# Power.net
KiCad netlist of a schematic drawn in Altium Designer
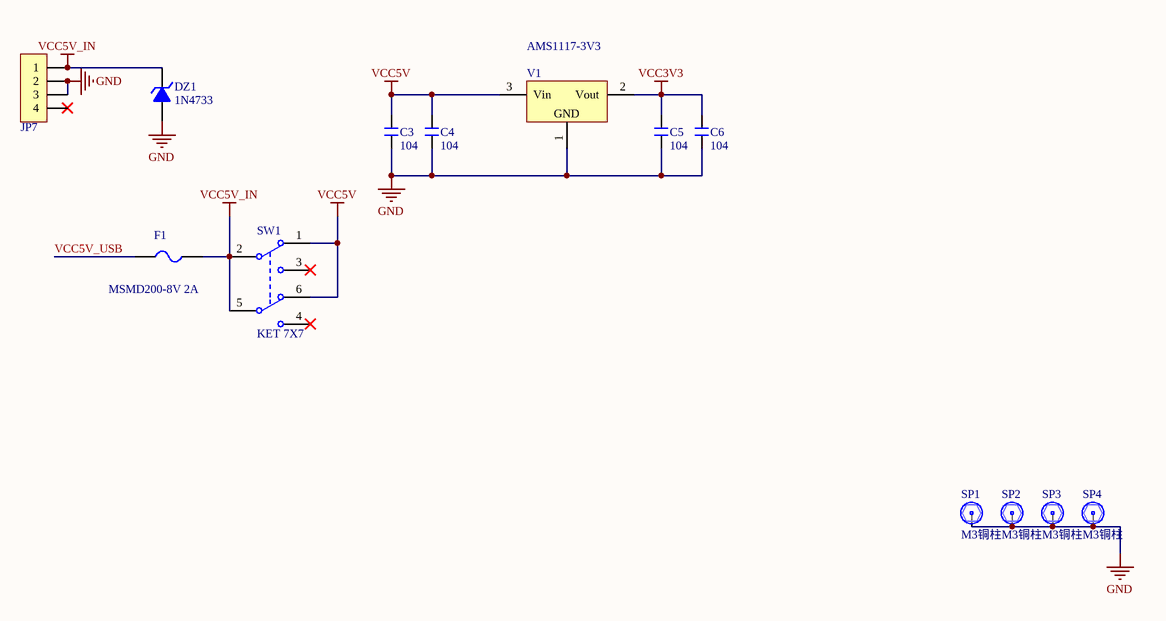
[diagram p0: Power.SchDoc]

(export (version "E")
  (design (tool "Eeschema 10.0.6"))
  (components
    (comp (ref "C3")
      (value "104")
      (footprint "C 1812_L")
      (description "无极性贴片电容")
      (fields (field (name "版权归属") "源创客"))
      (libsource (lib "3.1   - 电阻-电容-电感") (part "C"))
    )
    (comp (ref "C4")
      (value "104")
      (footprint "C 1812_L")
      (description "无极性贴片电容")
      (fields (field (name "版权归属") "源创客"))
      (libsource (lib "3.1   - 电阻-电容-电感") (part "C"))
    )
    (comp (ref "C5")
      (value "104")
      (footprint "C 1206_M")
      (description "无极性贴片电容")
      (fields (field (name "版权归属") "源创客"))
      (libsource (lib "3.1   - 电阻-电容-电感") (part "C"))
    )
    (comp (ref "C6")
      (value "104")
      (footprint "C 1206_M")
      (description "无极性贴片电容")
      (fields (field (name "版权归属") "源创客"))
      (libsource (lib "3.1   - 电阻-电容-电感") (part "C"))
    )
    (comp (ref "DZ1")
      (value "1N4733")
      (footprint "SMA")
      (description "5.1V/1W稳压管")
      (fields (field (name "版权归属") "源创客"))
      (libsource (lib "8.1   - 二极管-整流桥") (part "1N4733"))
    )
    (comp (ref "F1")
      (value "MSMD200-8V 2A")
      (footprint "FU 1210")
      (description "贴片保险丝")
      (fields (field (name "版权归属") "源创客"))
      (libsource (lib "10.1 - 保险丝-晶振") (part "FU"))
    )
    (comp (ref "JP7")
      (value "HDR-1X4")
      (footprint "VH3.96-LI-4P")
      (description "4P接插件")
      (fields (field (name "版权归属") "源创客"))
      (libsource (lib "4.8   - 接插件-脚距3.96") (part "Header 4"))
    )
    (comp (ref "SP1")
      (value "M3铜柱")
      (footprint "M3x4_L")
      (description "铜柱")
      (fields (field (name "版权归属") "源创客"))
      (libsource (lib "15.1 - 未分类器件") (part "铜柱小焊盘"))
    )
    (comp (ref "SP2")
      (value "M3铜柱")
      (footprint "M3x4_L")
      (description "铜柱")
      (fields (field (name "版权归属") "源创客"))
      (libsource (lib "15.1 - 未分类器件") (part "铜柱小焊盘"))
    )
    (comp (ref "SP3")
      (value "M3铜柱")
      (footprint "M3x4_L")
      (description "铜柱")
      (fields (field (name "版权归属") "源创客"))
      (libsource (lib "15.1 - 未分类器件") (part "铜柱小焊盘"))
    )
    (comp (ref "SP4")
      (value "M3铜柱")
      (footprint "M3x4_L")
      (description "铜柱")
      (fields (field (name "版权归属") "源创客"))
      (libsource (lib "15.1 - 未分类器件") (part "铜柱小焊盘"))
    )
    (comp (ref "SW1")
      (value "KET 7X7")
      (footprint "KFT DIP-7X7")
      (description "7*7自锁开关")
      (fields (field (name "版权归属") "源创客"))
      (libsource (lib "5.1   - 按键-开关") (part "KET 7X7"))
    )
    (comp (ref "V1")
      (value "AMS1117-3V3")
      (footprint "SOT223_L")
      (description "三端稳压芯片")
      (fields (field (name "版权归属") "源创客"))
      (libsource (lib "1.3   - 电源类芯片") (part "AMS1117"))
    )
  )
  (nets
    (net (code "1") (name "/VCC5V_USB") (class "Default")
      (node (ref "F1") (pin "1") (pinfunction "1_1") (pintype "passive"))
    )
    (net (code "2") (name "GND") (class "Default")
      (node (ref "C3") (pin "1") (pinfunction "1_1") (pintype "passive"))
      (node (ref "C4") (pin "1") (pinfunction "1_1") (pintype "passive"))
      (node (ref "C5") (pin "1") (pinfunction "1_1") (pintype "passive"))
      (node (ref "C6") (pin "1") (pinfunction "1_1") (pintype "passive"))
      (node (ref "DZ1") (pin "1") (pinfunction "A_1") (pintype "passive"))
      (node (ref "JP7") (pin "2") (pinfunction "2_2") (pintype "passive"))
      (node (ref "JP7") (pin "3") (pinfunction "3_3") (pintype "passive"))
      (node (ref "SP1") (pin "1") (pinfunction "1_1") (pintype "passive"))
      (node (ref "SP2") (pin "1") (pinfunction "1_1") (pintype "passive"))
      (node (ref "SP3") (pin "1") (pinfunction "1_1") (pintype "passive"))
      (node (ref "SP4") (pin "1") (pinfunction "1_1") (pintype "passive"))
      (node (ref "V1") (pin "1") (pinfunction "GND_1") (pintype "passive"))
    )
    (net (code "3") (name "VCC3V3") (class "Default")
      (node (ref "C5") (pin "2") (pinfunction "2_2") (pintype "passive"))
      (node (ref "C6") (pin "2") (pinfunction "2_2") (pintype "passive"))
      (node (ref "V1") (pin "2") (pinfunction "Vout_2") (pintype "passive"))
    )
    (net (code "4") (name "VCC5V") (class "Default")
      (node (ref "C3") (pin "2") (pinfunction "2_2") (pintype "passive"))
      (node (ref "C4") (pin "2") (pinfunction "2_2") (pintype "passive"))
      (node (ref "SW1") (pin "1") (pinfunction "NC1_1") (pintype "passive"))
      (node (ref "SW1") (pin "6") (pinfunction "NC2_6") (pintype "passive"))
      (node (ref "V1") (pin "3") (pinfunction "Vin_3") (pintype "passive"))
    )
    (net (code "5") (name "VCC5V_IN") (class "Default")
      (node (ref "DZ1") (pin "2") (pinfunction "K_2") (pintype "passive"))
      (node (ref "F1") (pin "2") (pinfunction "2_2") (pintype "passive"))
      (node (ref "JP7") (pin "1") (pinfunction "1_1") (pintype "passive"))
      (node (ref "SW1") (pin "2") (pinfunction "COM2_2") (pintype "passive"))
      (node (ref "SW1") (pin "5") (pinfunction "COM2_5") (pintype "passive"))
    )
    (net (code "6") (name "unconnected-(JP7-Pad4)") (class "Default")
      (node (ref "JP7") (pin "4") (pinfunction "4_4") (pintype "passive+no_connect"))
    )
    (net (code "7") (name "unconnected-(SW1-NO1-Pad3)") (class "Default")
      (node (ref "SW1") (pin "3") (pinfunction "NO1_3") (pintype "passive+no_connect"))
    )
    (net (code "8") (name "unconnected-(SW1-NO2-Pad4)") (class "Default")
      (node (ref "SW1") (pin "4") (pinfunction "NO2_4") (pintype "passive+no_connect"))
    )
  )
)
